# PWR_TPS8268180.net
KiCad netlist of a schematic drawn in Altium Designer
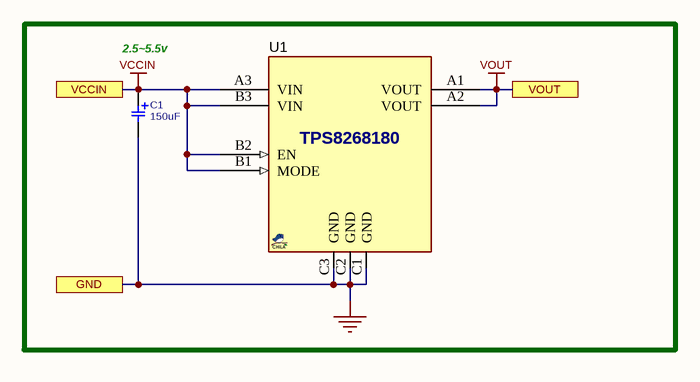
[diagram p0: PWR_TPS8268180.SchDoc]

(export (version "E")
  (design (tool "Eeschema 10.0.6"))
  (components
    (comp (ref "C1")
      (value "150uF")
      (footprint "C_TN_3528")
      (description "CAP, SMD, TAN,")
      (fields (field (name "MANF") "KEMET") (field (name "MANF_P#") "T520B157M006ATE025"))
      (libsource (lib "passive_smd") (part "CAP_SMD_TAN_3528"))
    )
    (comp (ref "U1")
      (value "TPS8268180")
      (footprint "PSON65_8T_3X3")
      (description "DC2DC Switching MODULE, Buck, 1.6A, Fixed, 2.5MHz, integrated Inductor")
      (fields (field (name "MANF") "Texas Instruments") (field (name "MANF_P#") "TPS8268180SIP"))
      (libsource (lib "pwr_switching_module") (part "VREG_TPS8268180_BGA9"))
    )
  )
  (nets
    (net (code "1") (name "GND") (class "Default")
      (node (ref "C1") (pin "2") (pinfunction "2_2") (pintype "passive"))
      (node (ref "U1") (pin "C1") (pinfunction "GND_C1") (pintype "power_in"))
      (node (ref "U1") (pin "C2") (pinfunction "GND_C2") (pintype "power_in"))
      (node (ref "U1") (pin "C3") (pinfunction "GND_C3") (pintype "power_in"))
    )
    (net (code "2") (name "VCCIN") (class "Default")
      (node (ref "C1") (pin "1") (pinfunction "1_1") (pintype "passive"))
      (node (ref "U1") (pin "A3") (pinfunction "VIN_A3") (pintype "power_in"))
      (node (ref "U1") (pin "B1") (pinfunction "MODE_B1") (pintype "input"))
      (node (ref "U1") (pin "B2") (pinfunction "EN_B2") (pintype "input"))
      (node (ref "U1") (pin "B3") (pinfunction "VIN_B3") (pintype "power_in"))
    )
    (net (code "3") (name "VOUT") (class "Default")
      (node (ref "U1") (pin "A1") (pinfunction "VOUT_A1") (pintype "power_in"))
      (node (ref "U1") (pin "A2") (pinfunction "VOUT_A2") (pintype "power_in"))
    )
  )
)
